# Mestrado_Roger.net
KiCad netlist of a schematic drawn in Altium Designer
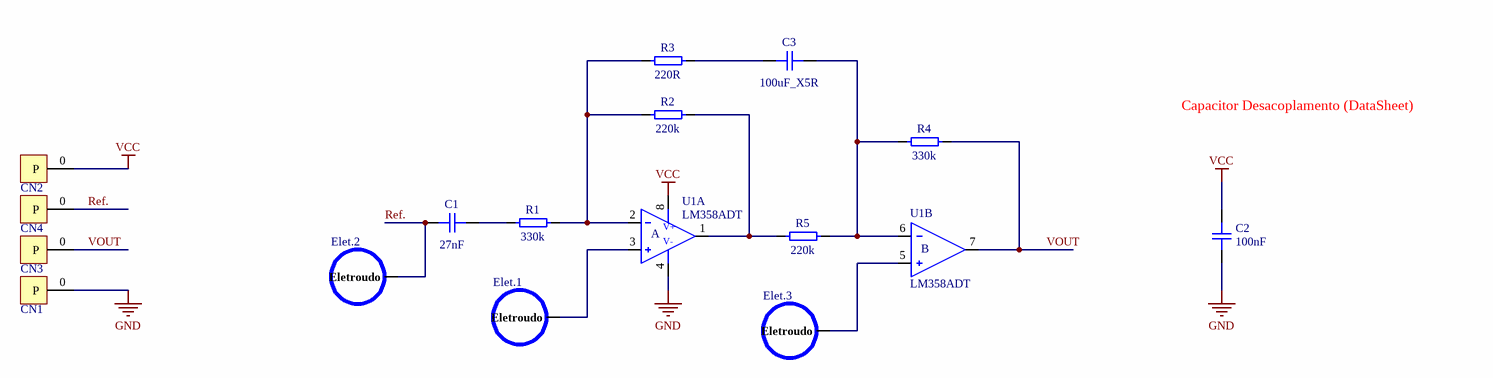
[diagram p0: Mestrado_Roger.SchDoc]

(export (version "E")
  (design (tool "Eeschema 10.0.6"))
  (components
    (comp (ref "C1")
      (value "27nF")
      (footprint "SMD_C_0603")
      (description "0.027 µF ±10% 25V Ceramic Capacitor X7R 0603 (1608 Metric)")
      (fields
        (field (name "PART NUMBER") "GMC10X7R273K25NT")
        (field (name "MANUFACTURER") "Cal-Chip Electronics, Inc.")
      )
      (libsource (lib "Bib_LOTUS") (part "Cap_Cer._0.027uF_10%_25V_SMD(0603)"))
    )
    (comp (ref "C2")
      (value "100nF")
      (footprint "SMD_C_0603")
      (description "0.1 µF ±10% 50V Ceramic Capacitor X7R 0603 (1608 Metric)")
      (fields
        (field (name "PART NUMBER") "C1608X7R1H104K080AA")
        (field (name "MANUFACTURER") "TDK Corporation")
      )
      (libsource (lib "Bib_LOTUS") (part "Cap_Cer._100nF_10%_50V_SMD(0603)"))
    )
    (comp (ref "C3")
      (value "100uF_X5R")
      (footprint "SMD_C_0805")
      (description "100 µF ±20% 4V Ceramic Capacitor X5R 0805 (2012 Metric)")
      (fields
        (field (name "PART NUMBER") "GRM21BR60G107ME11L")
        (field (name "MANUFACTURER") "Murata Electronics")
      )
      (libsource (lib "Bib_LOTUS") (part "Cap_Cer._100uF_20%_4V_SMD(0805)"))
    )
    (comp (ref "CN1") (value "Pad") (footprint "Pad") (libsource (lib "Conector") (part "Pad")))
    (comp (ref "CN2") (value "Pad") (footprint "Pad") (libsource (lib "Conector") (part "Pad")))
    (comp (ref "CN3") (value "Pad") (footprint "Pad") (libsource (lib "Conector") (part "Pad")))
    (comp (ref "CN4") (value "Pad") (footprint "Pad") (libsource (lib "Conector") (part "Pad")))
    (comp (ref "Elet.1")
      (value "Circuito_Eletroudo")
      (footprint "Eletroudo")
      (libsource (lib "Bib_LOTUS") (part "Circuito_Eletroudo"))
    )
    (comp (ref "Elet.2")
      (value "Circuito_Eletroudo")
      (footprint "Eletroudo")
      (libsource (lib "Bib_LOTUS") (part "Circuito_Eletroudo"))
    )
    (comp (ref "Elet.3")
      (value "Circuito_Eletroudo")
      (footprint "Eletroudo")
      (libsource (lib "Bib_LOTUS") (part "Circuito_Eletroudo"))
    )
    (comp (ref "R1")
      (value "330k")
      (footprint "SMD_R0603_F")
      (description "330 kOhms ±1% 0.1W, 1/10W Chip Resistor 0603 (1608 Metric) Moisture Resistant Thick Film")
      (fields (field (name "PART NUMBER") "RC0603FR-07330KL") (field (name "MANUFACTURER") "YAGEO"))
      (libsource (lib "Bib_LOTUS") (part "RES_330k_1%_0.1W_SMD(0603)"))
    )
    (comp (ref "R2")
      (value "220k")
      (footprint "SMD_R0603_F")
      (description "220 kOhms ±1% 0.1W, 1/10W Chip Resistor 0603 (1608 Metric) Moisture Resistant Thick Film")
      (fields (field (name "PART NUMBER") "RC0603FR-07220KL") (field (name "MANUFACTURER") "YAGEO"))
      (libsource (lib "Bib_LOTUS") (part "RES_220k_1%_0.1W_SMD(0603)"))
    )
    (comp (ref "R3")
      (value "220R")
      (footprint "SMD_R0603_F")
      (description "220 Ohms ±1% 0.1W, 1/10W Chip Resistor 0603 (1608 Metric) Moisture Resistant Thick Film")
      (fields (field (name "PART NUMBER") "RC0603FR-07220RL") (field (name "MANUFACTURER") "YAGEO"))
      (libsource (lib "Bib_LOTUS") (part "RES_220R_1%_0.1W_SMD(0603)"))
    )
    (comp (ref "R4")
      (value "330k")
      (footprint "SMD_R0603_F")
      (description "330 kOhms ±1% 0.1W, 1/10W Chip Resistor 0603 (1608 Metric) Moisture Resistant Thick Film")
      (fields (field (name "PART NUMBER") "RC0603FR-07330KL") (field (name "MANUFACTURER") "YAGEO"))
      (libsource (lib "Bib_LOTUS") (part "RES_330k_1%_0.1W_SMD(0603)"))
    )
    (comp (ref "R5")
      (value "220k")
      (footprint "SMD_R0603_F")
      (description "220 kOhms ±1% 0.1W, 1/10W Chip Resistor 0603 (1608 Metric) Moisture Resistant Thick Film")
      (fields (field (name "PART NUMBER") "RC0603FR-07220KL") (field (name "MANUFACTURER") "YAGEO"))
      (libsource (lib "Bib_LOTUS") (part "RES_220k_1%_0.1W_SMD(0603)"))
    )
    (comp (ref "U1")
      (value "LM358ADT")
      (footprint "SOIC-8")
      (description "Uso geral Amplificador 2 Circuito 8-SOIC")
      (fields (field (name "MANUFACTURER") "STMicroelectronics"))
      (libsource (lib "Bib_LOTUS") (part "Amp_LM358ADT"))
    )
  )
  (nets
    (net (code "1") (name "/Ref.") (class "Default")
      (node (ref "C1") (pin "1") (pinfunction "1_1") (pintype "passive"))
      (node (ref "CN4") (pin "0") (pinfunction "P_0") (pintype "passive"))
      (node (ref "Elet.2") (pin "0") (pinfunction "Eletroudo_0") (pintype "passive"))
    )
    (net (code "2") (name "/VOUT") (class "Default")
      (node (ref "CN3") (pin "0") (pinfunction "P_0") (pintype "passive"))
      (node (ref "R4") (pin "1") (pinfunction "1_1") (pintype "passive"))
      (node (ref "U1") (pin "7") (pinfunction "OUT2_7") (pintype "passive"))
    )
    (net (code "3") (name "GND") (class "Default")
      (node (ref "C2") (pin "2") (pinfunction "2_2") (pintype "passive"))
      (node (ref "CN1") (pin "0") (pinfunction "P_0") (pintype "passive"))
      (node (ref "U1") (pin "4") (pinfunction "GND_4") (pintype "passive"))
    )
    (net (code "4") (name "Net-(C1-Pad2)") (class "Default")
      (node (ref "C1") (pin "2") (pinfunction "2_2") (pintype "passive"))
      (node (ref "R1") (pin "1") (pinfunction "1_1") (pintype "passive"))
    )
    (net (code "5") (name "Net-(C3-Pad1)") (class "Default")
      (node (ref "C3") (pin "1") (pinfunction "1_1") (pintype "passive"))
      (node (ref "R3") (pin "2") (pinfunction "2_2") (pintype "passive"))
    )
    (net (code "6") (name "Net-(Elet.1-Eletroudo)") (class "Default")
      (node (ref "Elet.1") (pin "0") (pinfunction "Eletroudo_0") (pintype "passive"))
      (node (ref "U1") (pin "3") (pinfunction "IN1(+)_3") (pintype "passive"))
    )
    (net (code "7") (name "Net-(Elet.3-Eletroudo)") (class "Default")
      (node (ref "Elet.3") (pin "0") (pinfunction "Eletroudo_0") (pintype "passive"))
      (node (ref "U1") (pin "5") (pinfunction "IN2(+)_5") (pintype "passive"))
    )
    (net (code "8") (name "Net-(U1A-IN1(-))") (class "Default")
      (node (ref "R1") (pin "2") (pinfunction "2_2") (pintype "passive"))
      (node (ref "R2") (pin "1") (pinfunction "1_1") (pintype "passive"))
      (node (ref "R3") (pin "1") (pinfunction "1_1") (pintype "passive"))
      (node (ref "U1") (pin "2") (pinfunction "IN1(-)_2") (pintype "passive"))
    )
    (net (code "9") (name "Net-(U1A-OUT1)") (class "Default")
      (node (ref "R2") (pin "2") (pinfunction "2_2") (pintype "passive"))
      (node (ref "R5") (pin "1") (pinfunction "1_1") (pintype "passive"))
      (node (ref "U1") (pin "1") (pinfunction "OUT1_1") (pintype "passive"))
    )
    (net (code "10") (name "Net-(U1B-IN2(-))") (class "Default")
      (node (ref "C3") (pin "2") (pinfunction "2_2") (pintype "passive"))
      (node (ref "R4") (pin "2") (pinfunction "2_2") (pintype "passive"))
      (node (ref "R5") (pin "2") (pinfunction "2_2") (pintype "passive"))
      (node (ref "U1") (pin "6") (pinfunction "IN2(-)_6") (pintype "passive"))
    )
    (net (code "11") (name "VCC") (class "Default")
      (node (ref "C2") (pin "1") (pinfunction "1_1") (pintype "passive"))
      (node (ref "CN2") (pin "0") (pinfunction "P_0") (pintype "passive"))
      (node (ref "U1") (pin "8") (pinfunction "VCC_8") (pintype "passive"))
    )
  )
)
